# QRE1113-4.net
KiCad netlist of a schematic drawn in Altium Designer
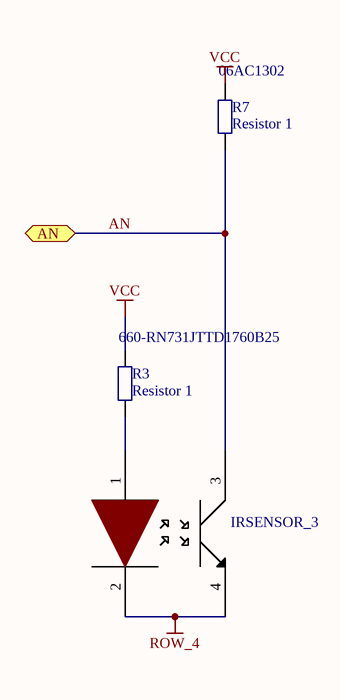
[diagram p0: QRE1113-4.SchDoc]

(export (version "E")
  (design (tool "Eeschema 10.0.6"))
  (components
    (comp (ref "IRSENSOR_3")
      (value "QRE1113GR")
      (footprint "QRE1113:QRE1113GR")
      (libsource (lib "Keyboard Library") (part "QRE1113GR"))
    )
    (comp (ref "R3")
      (value "Resistor 1")
      (footprint "R-0603")
      (description "Resistor")
      (fields (field (name "SUPPLIER PART NUMBER 1") "660-RN731JTTD1760B25"))
      (libsource (lib "") (part "Resistor 1_1"))
    )
    (comp (ref "R7")
      (value "Resistor 1")
      (footprint "R-0603")
      (description "Resistor")
      (fields (field (name "SUPPLIER PART NUMBER 1") "06AC1302"))
      (libsource (lib "Max Library") (part "Resistor 1"))
    )
  )
  (nets
    (net (code "1") (name "/AN") (class "Default")
      (node (ref "IRSENSOR_3") (pin "3") (pinfunction "3_3") (pintype "passive"))
      (node (ref "R7") (pin "2") (pinfunction "2_2") (pintype "passive"))
    )
    (net (code "2") (name "Net-(IRSENSOR_3-Pad1)") (class "Default")
      (node (ref "IRSENSOR_3") (pin "1") (pinfunction "1_1") (pintype "passive"))
      (node (ref "R3") (pin "1") (pinfunction "1_1") (pintype "passive"))
    )
    (net (code "3") (name "ROW_3") (class "Default")
      (node (ref "IRSENSOR_3") (pin "2") (pinfunction "2_2") (pintype "passive"))
      (node (ref "IRSENSOR_3") (pin "4") (pinfunction "4_4") (pintype "passive"))
    )
    (net (code "4") (name "VCC") (class "Default")
      (node (ref "R3") (pin "2") (pinfunction "2_2") (pintype "passive"))
      (node (ref "R7") (pin "1") (pinfunction "1_1") (pintype "passive"))
    )
  )
)
